# remote_control.net
KiCad netlist of a schematic drawn in EAGLE
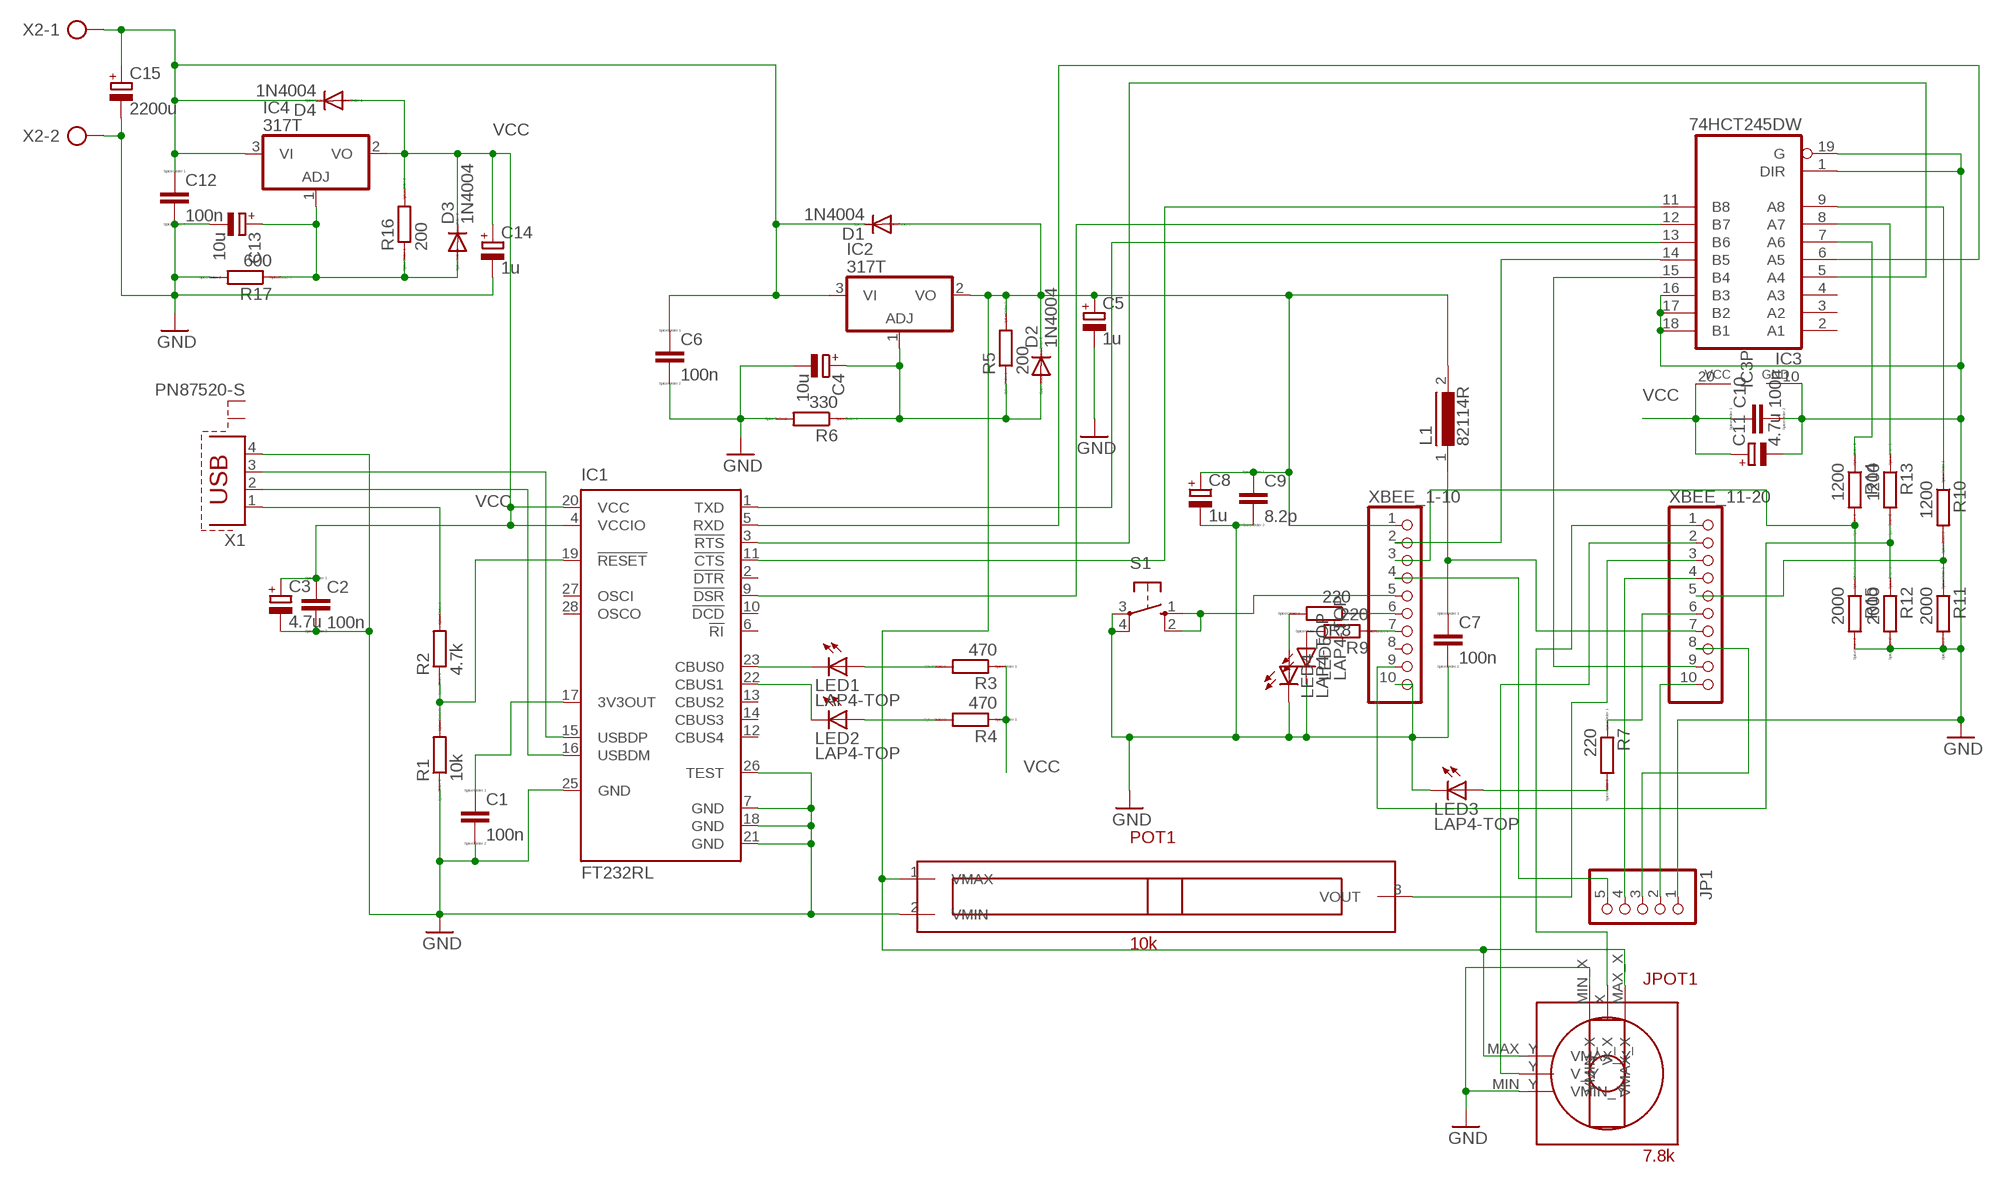
[diagram p0: schematic, sheet 1]

(export (version "E")
  (design (tool "Eeschema 10.0.6"))
  (components
    (comp (ref "C1")
      (value "100n")
      (footprint "eagle-import:C025-030X050")
      (libsource (lib "eagle-import") (part "C-EU025-030X050"))
    )
    (comp (ref "C2")
      (value "100n")
      (footprint "eagle-import:C0805K")
      (libsource (lib "eagle-import") (part "C-EUC0805K"))
    )
    (comp (ref "C3")
      (value "4.7u")
      (footprint "eagle-import:153CLV-0605")
      (libsource (lib "eagle-import") (part "CPOL-EU153CLV-0605"))
    )
    (comp (ref "C4")
      (value "10u")
      (footprint "eagle-import:E5-8,5")
      (libsource (lib "eagle-import") (part "CPOL-EUE5-8.5"))
    )
    (comp (ref "C5")
      (value "1u")
      (footprint "eagle-import:E5-8,5")
      (libsource (lib "eagle-import") (part "CPOL-EUE5-8.5"))
    )
    (comp (ref "C6")
      (value "100n")
      (footprint "eagle-import:C025-030X050")
      (libsource (lib "eagle-import") (part "C-EU025-030X050"))
    )
    (comp (ref "C7")
      (value "100n")
      (footprint "eagle-import:C025-030X050")
      (libsource (lib "eagle-import") (part "C-EU025-030X050"))
    )
    (comp (ref "C8")
      (value "1u")
      (footprint "eagle-import:E5-8,5")
      (libsource (lib "eagle-import") (part "CPOL-EUE5-8.5"))
    )
    (comp (ref "C9")
      (value "8.2p")
      (footprint "eagle-import:C025-030X050")
      (libsource (lib "eagle-import") (part "C-EU025-030X050"))
    )
    (comp (ref "C10")
      (value "100n")
      (footprint "eagle-import:C0805K")
      (libsource (lib "eagle-import") (part "C-EUC0805K"))
    )
    (comp (ref "C11")
      (value "4.7u")
      (footprint "eagle-import:153CLV-0605")
      (libsource (lib "eagle-import") (part "CPOL-EU153CLV-0605"))
    )
    (comp (ref "C12")
      (value "100n")
      (footprint "eagle-import:C025-030X050")
      (libsource (lib "eagle-import") (part "C-EU025-030X050"))
    )
    (comp (ref "C13")
      (value "10u")
      (footprint "eagle-import:E5-8,5")
      (libsource (lib "eagle-import") (part "CPOL-EUE5-8.5"))
    )
    (comp (ref "C14")
      (value "1u")
      (footprint "eagle-import:E5-8,5")
      (libsource (lib "eagle-import") (part "CPOL-EUE5-8.5"))
    )
    (comp (ref "C15")
      (value "2200u")
      (footprint "eagle-import:EB20D")
      (libsource (lib "eagle-import") (part "CPOL-EUE10-20"))
    )
    (comp (ref "D1")
      (value "1N4004")
      (footprint "eagle-import:DO41-10")
      (libsource (lib "eagle-import") (part "1N4004"))
    )
    (comp (ref "D2")
      (value "1N4004")
      (footprint "eagle-import:DO41-10")
      (libsource (lib "eagle-import") (part "1N4004"))
    )
    (comp (ref "D3")
      (value "1N4004")
      (footprint "eagle-import:DO41-10")
      (libsource (lib "eagle-import") (part "1N4004"))
    )
    (comp (ref "D4")
      (value "1N4004")
      (footprint "eagle-import:DO41-10")
      (libsource (lib "eagle-import") (part "1N4004"))
    )
    (comp (ref "IC1")
      (value "FT232RL")
      (footprint "eagle-import:SSOP28")
      (libsource (lib "eagle-import") (part "FT232RL"))
    )
    (comp (ref "IC2")
      (value "317T")
      (footprint "eagle-import:TO220H")
      (libsource (lib "eagle-import") (part "317T"))
    )
    (comp (ref "IC3")
      (value "74HCT245DW")
      (footprint "eagle-import:SO20W")
      (libsource (lib "eagle-import") (part "74245DWHCT"))
    )
    (comp (ref "IC4")
      (value "317T")
      (footprint "eagle-import:TO220H")
      (libsource (lib "eagle-import") (part "317T"))
    )
    (comp (ref "JP1")
      (value "PINHD-1X5")
      (footprint "eagle-import:1X05")
      (libsource (lib "eagle-import") (part "PINHD-1X5"))
    )
    (comp (ref "JPOT1")
      (value "7.8k")
      (footprint "eagle-import:DIL")
      (libsource (lib "eagle-import") (part "JOYSTICK_POTIP"))
    )
    (comp (ref "L1")
      (value "82114R")
      (footprint "eagle-import:82114R")
      (libsource (lib "eagle-import") (part "82114R"))
    )
    (comp (ref "LED1")
      (value "LAP4-TOP")
      (footprint "eagle-import:P47F-TOP")
      (libsource (lib "eagle-import") (part "P4-TOPLA"))
    )
    (comp (ref "LED2")
      (value "LAP4-TOP")
      (footprint "eagle-import:P47F-TOP")
      (libsource (lib "eagle-import") (part "P4-TOPLA"))
    )
    (comp (ref "LED3")
      (value "LAP4-TOP")
      (footprint "eagle-import:P47F-TOP")
      (libsource (lib "eagle-import") (part "P4-TOPLA"))
    )
    (comp (ref "LED4")
      (value "LAP4-TOP")
      (footprint "eagle-import:P47F-TOP")
      (libsource (lib "eagle-import") (part "P4-TOPLA"))
    )
    (comp (ref "LED5")
      (value "LAP4-TOP")
      (footprint "eagle-import:P47F-TOP")
      (libsource (lib "eagle-import") (part "P4-TOPLA"))
    )
    (comp (ref "POT1")
      (value "10k")
      (footprint "eagle-import:DIL")
      (libsource (lib "eagle-import") (part "SCHIEBEPOTENTIOMETER"))
    )
    (comp (ref "R1")
      (value "10k")
      (footprint "eagle-import:0207_10")
      (libsource (lib "eagle-import") (part "R-EU_0207_10"))
    )
    (comp (ref "R2")
      (value "4.7k")
      (footprint "eagle-import:0207_10")
      (libsource (lib "eagle-import") (part "R-EU_0207_10"))
    )
    (comp (ref "R3")
      (value "470")
      (footprint "eagle-import:0207_10")
      (libsource (lib "eagle-import") (part "R-EU_0207_10"))
    )
    (comp (ref "R4")
      (value "470")
      (footprint "eagle-import:0207_10")
      (libsource (lib "eagle-import") (part "R-EU_0207_10"))
    )
    (comp (ref "R5")
      (value "200")
      (footprint "eagle-import:0411_15")
      (libsource (lib "eagle-import") (part "R-EU_0411_15"))
    )
    (comp (ref "R6")
      (value "330")
      (footprint "eagle-import:0411_15")
      (libsource (lib "eagle-import") (part "R-EU_0411_15"))
    )
    (comp (ref "R7")
      (value "220")
      (footprint "eagle-import:0207_10")
      (libsource (lib "eagle-import") (part "R-EU_0207_10"))
    )
    (comp (ref "R8")
      (value "220")
      (footprint "eagle-import:0207_10")
      (libsource (lib "eagle-import") (part "R-EU_0207_10"))
    )
    (comp (ref "R9")
      (value "220")
      (footprint "eagle-import:0207_10")
      (libsource (lib "eagle-import") (part "R-EU_0207_10"))
    )
    (comp (ref "R10")
      (value "1200")
      (footprint "eagle-import:0207_10")
      (libsource (lib "eagle-import") (part "R-EU_0207_10"))
    )
    (comp (ref "R11")
      (value "2000")
      (footprint "eagle-import:0207_10")
      (libsource (lib "eagle-import") (part "R-EU_0207_10"))
    )
    (comp (ref "R12")
      (value "2000")
      (footprint "eagle-import:0207_10")
      (libsource (lib "eagle-import") (part "R-EU_0207_10"))
    )
    (comp (ref "R13")
      (value "1200")
      (footprint "eagle-import:0207_10")
      (libsource (lib "eagle-import") (part "R-EU_0207_10"))
    )
    (comp (ref "R14")
      (value "1200")
      (footprint "eagle-import:0207_10")
      (libsource (lib "eagle-import") (part "R-EU_0207_10"))
    )
    (comp (ref "R15")
      (value "2000")
      (footprint "eagle-import:0207_10")
      (libsource (lib "eagle-import") (part "R-EU_0207_10"))
    )
    (comp (ref "R16")
      (value "200")
      (footprint "eagle-import:0411_15")
      (libsource (lib "eagle-import") (part "R-EU_0411_15"))
    )
    (comp (ref "R17")
      (value "600")
      (footprint "eagle-import:0411_15")
      (libsource (lib "eagle-import") (part "R-EU_0411_15"))
    )
    (comp (ref "S1")
      (value "40-XX")
      (footprint "eagle-import:B3F-40XX")
      (fields (field (name "MF") "OMRON COMPONENTS USA") (field (name "MPN") "B3F-4000"))
      (libsource (lib "eagle-import") (part "40-XX"))
    )
    (comp (ref "X1")
      (value "PN87520-S")
      (footprint "eagle-import:PN87520-S")
      (libsource (lib "eagle-import") (part "PN87520-S"))
    )
    (comp (ref "X2")
      (value "AK300/2")
      (footprint "eagle-import:AK300_2")
      (libsource (lib "eagle-import") (part "AK300/2"))
    )
    (comp (ref "XBEE_1-10")
      (value "PINHD-1X10M")
      (footprint "eagle-import:1X10M")
      (libsource (lib "eagle-import") (part "PINHD-1X10M"))
    )
    (comp (ref "XBEE_11-20")
      (value "PINHD-1X10M")
      (footprint "eagle-import:1X10M")
      (libsource (lib "eagle-import") (part "PINHD-1X10M"))
    )
  )
  (nets
    (net (code "1") (name "/VCC") (class "Default")
      (node (ref "C10") (pin "1") (pinfunction "1_1") (pintype "passive"))
      (node (ref "C11") (pin "+") (pinfunction "+_+") (pintype "passive"))
      (node (ref "C14") (pin "+") (pinfunction "+_+") (pintype "passive"))
      (node (ref "C2") (pin "1") (pinfunction "1_1") (pintype "passive"))
      (node (ref "C3") (pin "+") (pinfunction "+_+") (pintype "passive"))
      (node (ref "D3") (pin "C") (pinfunction "C_C") (pintype "passive"))
      (node (ref "D4") (pin "A") (pinfunction "A_A") (pintype "passive"))
      (node (ref "IC1") (pin "20") (pinfunction "VCC_20") (pintype "power_in"))
      (node (ref "IC1") (pin "4") (pinfunction "VCCIO_4") (pintype "power_in"))
      (node (ref "IC3") (pin "20") (pinfunction "VCC_20") (pintype "power_in"))
      (node (ref "IC4") (pin "2") (pinfunction "VO_2") (pintype "passive"))
      (node (ref "R16") (pin "2") (pinfunction "2_2") (pintype "passive"))
      (node (ref "R3") (pin "1") (pinfunction "1_1") (pintype "passive"))
      (node (ref "R4") (pin "1") (pinfunction "1_1") (pintype "passive"))
    )
    (net (code "2") (name "GND") (class "Default")
      (node (ref "C1") (pin "2") (pinfunction "2_2") (pintype "passive"))
      (node (ref "C10") (pin "2") (pinfunction "2_2") (pintype "passive"))
      (node (ref "C11") (pin "-") (pinfunction "-_-") (pintype "passive"))
      (node (ref "C12") (pin "2") (pinfunction "2_2") (pintype "passive"))
      (node (ref "C13") (pin "-") (pinfunction "-_-") (pintype "passive"))
      (node (ref "C14") (pin "-") (pinfunction "-_-") (pintype "passive"))
      (node (ref "C15") (pin "-") (pinfunction "-_-") (pintype "passive"))
      (node (ref "C2") (pin "2") (pinfunction "2_2") (pintype "passive"))
      (node (ref "C3") (pin "-") (pinfunction "-_-") (pintype "passive"))
      (node (ref "C4") (pin "-") (pinfunction "-_-") (pintype "passive"))
      (node (ref "C5") (pin "-") (pinfunction "-_-") (pintype "passive"))
      (node (ref "C6") (pin "2") (pinfunction "2_2") (pintype "passive"))
      (node (ref "C7") (pin "2") (pinfunction "2_2") (pintype "passive"))
      (node (ref "C8") (pin "-") (pinfunction "-_-") (pintype "passive"))
      (node (ref "C9") (pin "2") (pinfunction "2_2") (pintype "passive"))
      (node (ref "IC1") (pin "18") (pinfunction "GND_18") (pintype "power_in"))
      (node (ref "IC1") (pin "21") (pinfunction "GND_21") (pintype "power_in"))
      (node (ref "IC1") (pin "25") (pinfunction "GND_25") (pintype "power_in"))
      (node (ref "IC1") (pin "26") (pinfunction "TEST_26") (pintype "input"))
      (node (ref "IC1") (pin "7") (pinfunction "GND_7") (pintype "power_in"))
      (node (ref "IC3") (pin "1") (pinfunction "DIR_1") (pintype "input"))
      (node (ref "IC3") (pin "10") (pinfunction "GND_10") (pintype "power_in"))
      (node (ref "IC3") (pin "16") (pinfunction "B3_16") (pintype "bidirectional"))
      (node (ref "IC3") (pin "17") (pinfunction "B2_17") (pintype "bidirectional"))
      (node (ref "IC3") (pin "18") (pinfunction "B1_18") (pintype "bidirectional"))
      (node (ref "IC3") (pin "19") (pinfunction "G_19") (pintype "input"))
      (node (ref "JP1") (pin "1") (pinfunction "1_1") (pintype "passive"))
      (node (ref "JPOT1") (pin "MIN_X") (pinfunction "VMIN_X_MIN_X") (pintype "bidirectional"))
      (node (ref "JPOT1") (pin "MIN_Y") (pinfunction "VMIN_Y_MIN_Y") (pintype "bidirectional"))
      (node (ref "LED3") (pin "C") (pinfunction "C_C") (pintype "passive"))
      (node (ref "LED4") (pin "C") (pinfunction "C_C") (pintype "passive"))
      (node (ref "LED5") (pin "C") (pinfunction "C_C") (pintype "passive"))
      (node (ref "POT1") (pin "2") (pinfunction "VMIN_2") (pintype "input"))
      (node (ref "R1") (pin "1") (pinfunction "1_1") (pintype "passive"))
      (node (ref "R11") (pin "2") (pinfunction "2_2") (pintype "passive"))
      (node (ref "R12") (pin "2") (pinfunction "2_2") (pintype "passive"))
      (node (ref "R15") (pin "2") (pinfunction "2_2") (pintype "passive"))
      (node (ref "R17") (pin "2") (pinfunction "2_2") (pintype "passive"))
      (node (ref "R6") (pin "2") (pinfunction "2_2") (pintype "passive"))
      (node (ref "S1") (pin "3") (pinfunction "P_3") (pintype "passive"))
      (node (ref "S1") (pin "4") (pinfunction "P1_4") (pintype "passive"))
      (node (ref "X1") (pin "4") (pinfunction "4_4") (pintype "passive"))
      (node (ref "X2") (pin "2") (pinfunction "KL_2") (pintype "passive"))
      (node (ref "XBEE_1-10") (pin "10") (pinfunction "10_10") (pintype "passive"))
    )
    (net (code "3") (name "Net-(C7-Pad1)") (class "Default")
      (node (ref "C7") (pin "1") (pinfunction "1_1") (pintype "passive"))
      (node (ref "L1") (pin "1") (pinfunction "1_1") (pintype "passive"))
      (node (ref "XBEE_11-20") (pin "7") (pinfunction "7_7") (pintype "passive"))
    )
    (net (code "4") (name "Net-(IC1-3V3OUT)") (class "Default")
      (node (ref "C1") (pin "1") (pinfunction "1_1") (pintype "passive"))
      (node (ref "IC1") (pin "17") (pinfunction "3V3OUT_17") (pintype "output"))
    )
    (net (code "5") (name "Net-(IC1-CBUS0)") (class "Default")
      (node (ref "IC1") (pin "23") (pinfunction "CBUS0_23") (pintype "bidirectional"))
      (node (ref "LED1") (pin "C") (pinfunction "C_C") (pintype "passive"))
    )
    (net (code "6") (name "Net-(IC1-CBUS1)") (class "Default")
      (node (ref "IC1") (pin "22") (pinfunction "CBUS1_22") (pintype "bidirectional"))
      (node (ref "LED2") (pin "C") (pinfunction "C_C") (pintype "passive"))
    )
    (net (code "7") (name "Net-(IC1-RXD)") (class "Default")
      (node (ref "IC1") (pin "5") (pinfunction "RXD_5") (pintype "input"))
      (node (ref "IC3") (pin "6") (pinfunction "A5_6") (pintype "bidirectional"))
    )
    (net (code "8") (name "Net-(IC1-TXD)") (class "Default")
      (node (ref "IC1") (pin "1") (pinfunction "TXD_1") (pintype "output"))
      (node (ref "IC3") (pin "13") (pinfunction "B6_13") (pintype "bidirectional"))
    )
    (net (code "9") (name "Net-(IC1-USBDM)") (class "Default")
      (node (ref "IC1") (pin "16") (pinfunction "USBDM_16") (pintype "bidirectional"))
      (node (ref "X1") (pin "2") (pinfunction "2_2") (pintype "passive"))
    )
    (net (code "10") (name "Net-(IC1-USBDP)") (class "Default")
      (node (ref "IC1") (pin "15") (pinfunction "USBDP_15") (pintype "bidirectional"))
      (node (ref "X1") (pin "3") (pinfunction "3_3") (pintype "passive"))
    )
    (net (code "11") (name "Net-(IC1-~{CTS})") (class "Default")
      (node (ref "IC1") (pin "11") (pinfunction "~{CTS}_11") (pintype "input"))
      (node (ref "IC3") (pin "11") (pinfunction "B8_11") (pintype "bidirectional"))
    )
    (net (code "12") (name "Net-(IC1-~{DSR})") (class "Default")
      (node (ref "IC1") (pin "9") (pinfunction "~{DSR}_9") (pintype "input"))
      (node (ref "IC3") (pin "12") (pinfunction "B7_12") (pintype "bidirectional"))
    )
    (net (code "13") (name "Net-(IC1-~{RESET})") (class "Default")
      (node (ref "IC1") (pin "19") (pinfunction "~{RESET}_19") (pintype "input"))
      (node (ref "R1") (pin "2") (pinfunction "2_2") (pintype "passive"))
      (node (ref "R2") (pin "1") (pinfunction "1_1") (pintype "passive"))
    )
    (net (code "14") (name "Net-(IC1-~{RTS})") (class "Default")
      (node (ref "IC1") (pin "3") (pinfunction "~{RTS}_3") (pintype "output"))
      (node (ref "IC3") (pin "5") (pinfunction "A4_5") (pintype "bidirectional"))
    )
    (net (code "15") (name "Net-(IC2-ADJ)") (class "Default")
      (node (ref "C4") (pin "+") (pinfunction "+_+") (pintype "passive"))
      (node (ref "D2") (pin "A") (pinfunction "A_A") (pintype "passive"))
      (node (ref "IC2") (pin "1") (pinfunction "ADJ_1") (pintype "input"))
      (node (ref "R5") (pin "1") (pinfunction "1_1") (pintype "passive"))
      (node (ref "R6") (pin "1") (pinfunction "1_1") (pintype "passive"))
    )
    (net (code "16") (name "Net-(IC2-VI)") (class "Default")
      (node (ref "C12") (pin "1") (pinfunction "1_1") (pintype "passive"))
      (node (ref "C15") (pin "+") (pinfunction "+_+") (pintype "passive"))
      (node (ref "C6") (pin "1") (pinfunction "1_1") (pintype "passive"))
      (node (ref "D1") (pin "C") (pinfunction "C_C") (pintype "passive"))
      (node (ref "D4") (pin "C") (pinfunction "C_C") (pintype "passive"))
      (node (ref "IC2") (pin "3") (pinfunction "VI_3") (pintype "input"))
      (node (ref "IC4") (pin "3") (pinfunction "VI_3") (pintype "input"))
      (node (ref "X2") (pin "1") (pinfunction "KL_1") (pintype "passive"))
    )
    (net (code "17") (name "Net-(IC2-VO)") (class "Default")
      (node (ref "C5") (pin "+") (pinfunction "+_+") (pintype "passive"))
      (node (ref "C8") (pin "+") (pinfunction "+_+") (pintype "passive"))
      (node (ref "C9") (pin "1") (pinfunction "1_1") (pintype "passive"))
      (node (ref "D1") (pin "A") (pinfunction "A_A") (pintype "passive"))
      (node (ref "D2") (pin "C") (pinfunction "C_C") (pintype "passive"))
      (node (ref "IC2") (pin "2") (pinfunction "VO_2") (pintype "passive"))
      (node (ref "JPOT1") (pin "MAX_X") (pinfunction "VMAX_X_MAX_X") (pintype "bidirectional"))
      (node (ref "JPOT1") (pin "MAX_Y") (pinfunction "VMAX_Y_MAX_Y") (pintype "bidirectional"))
      (node (ref "L1") (pin "2") (pinfunction "2_2") (pintype "passive"))
      (node (ref "POT1") (pin "1") (pinfunction "VMAX_1") (pintype "input"))
      (node (ref "R5") (pin "2") (pinfunction "2_2") (pintype "passive"))
      (node (ref "XBEE_1-10") (pin "1") (pinfunction "1_1") (pintype "passive"))
    )
    (net (code "18") (name "Net-(IC3A-A6)") (class "Default")
      (node (ref "IC3") (pin "7") (pinfunction "A6_7") (pintype "bidirectional"))
      (node (ref "R14") (pin "1") (pinfunction "1_1") (pintype "passive"))
    )
    (net (code "19") (name "Net-(IC3A-A7)") (class "Default")
      (node (ref "IC3") (pin "8") (pinfunction "A7_8") (pintype "bidirectional"))
      (node (ref "R13") (pin "1") (pinfunction "1_1") (pintype "passive"))
    )
    (net (code "20") (name "Net-(IC3A-A8)") (class "Default")
      (node (ref "IC3") (pin "9") (pinfunction "A8_9") (pintype "bidirectional"))
      (node (ref "R10") (pin "1") (pinfunction "1_1") (pintype "passive"))
    )
    (net (code "21") (name "Net-(IC3A-B4)") (class "Default")
      (node (ref "IC3") (pin "15") (pinfunction "B4_15") (pintype "bidirectional"))
      (node (ref "XBEE_11-20") (pin "9") (pinfunction "9_9") (pintype "passive"))
    )
    (net (code "22") (name "Net-(IC3A-B5)") (class "Default")
      (node (ref "IC3") (pin "14") (pinfunction "B5_14") (pintype "bidirectional"))
      (node (ref "XBEE_1-10") (pin "2") (pinfunction "2_2") (pintype "passive"))
    )
    (net (code "23") (name "Net-(IC4-ADJ)") (class "Default")
      (node (ref "C13") (pin "+") (pinfunction "+_+") (pintype "passive"))
      (node (ref "D3") (pin "A") (pinfunction "A_A") (pintype "passive"))
      (node (ref "IC4") (pin "1") (pinfunction "ADJ_1") (pintype "input"))
      (node (ref "R16") (pin "1") (pinfunction "1_1") (pintype "passive"))
      (node (ref "R17") (pin "1") (pinfunction "1_1") (pintype "passive"))
    )
    (net (code "24") (name "Net-(JP1-Pad2)") (class "Default")
      (node (ref "JP1") (pin "2") (pinfunction "2_2") (pintype "passive"))
      (node (ref "XBEE_11-20") (pin "10") (pinfunction "10_10") (pintype "passive"))
    )
    (net (code "25") (name "Net-(JP1-Pad3)") (class "Default")
      (node (ref "JP1") (pin "3") (pinfunction "3_3") (pintype "passive"))
      (node (ref "XBEE_11-20") (pin "8") (pinfunction "8_8") (pintype "passive"))
    )
    (net (code "26") (name "Net-(JP1-Pad4)") (class "Default")
      (node (ref "JP1") (pin "4") (pinfunction "4_4") (pintype "passive"))
      (node (ref "XBEE_11-20") (pin "4") (pinfunction "4_4") (pintype "passive"))
    )
    (net (code "27") (name "Net-(JP1-Pad5)") (class "Default")
      (node (ref "JP1") (pin "5") (pinfunction "5_5") (pintype "passive"))
      (node (ref "XBEE_1-10") (pin "4") (pinfunction "4_4") (pintype "passive"))
    )
    (net (code "28") (name "Net-(JPOT1-V_X)") (class "Default")
      (node (ref "JPOT1") (pin "X") (pinfunction "V_X_X") (pintype "bidirectional"))
      (node (ref "XBEE_11-20") (pin "1") (pinfunction "1_1") (pintype "passive"))
    )
    (net (code "29") (name "Net-(JPOT1-V_Y)") (class "Default")
      (node (ref "JPOT1") (pin "Y") (pinfunction "V_Y_Y") (pintype "bidirectional"))
      (node (ref "XBEE_11-20") (pin "2") (pinfunction "2_2") (pintype "passive"))
    )
    (net (code "30") (name "Net-(LED1-PadA)") (class "Default")
      (node (ref "LED1") (pin "A") (pinfunction "A_A") (pintype "passive"))
      (node (ref "R3") (pin "2") (pinfunction "2_2") (pintype "passive"))
    )
    (net (code "31") (name "Net-(LED2-PadA)") (class "Default")
      (node (ref "LED2") (pin "A") (pinfunction "A_A") (pintype "passive"))
      (node (ref "R4") (pin "2") (pinfunction "2_2") (pintype "passive"))
    )
    (net (code "32") (name "Net-(LED3-PadA)") (class "Default")
      (node (ref "LED3") (pin "A") (pinfunction "A_A") (pintype "passive"))
      (node (ref "R7") (pin "2") (pinfunction "2_2") (pintype "passive"))
    )
    (net (code "33") (name "Net-(LED4-PadA)") (class "Default")
      (node (ref "LED4") (pin "A") (pinfunction "A_A") (pintype "passive"))
      (node (ref "R8") (pin "2") (pinfunction "2_2") (pintype "passive"))
    )
    (net (code "34") (name "Net-(LED5-PadA)") (class "Default")
      (node (ref "LED5") (pin "A") (pinfunction "A_A") (pintype "passive"))
      (node (ref "R9") (pin "2") (pinfunction "2_2") (pintype "passive"))
    )
    (net (code "35") (name "Net-(POT1-VOUT)") (class "Default")
      (node (ref "POT1") (pin "3") (pinfunction "VOUT_3") (pintype "output"))
      (node (ref "XBEE_11-20") (pin "3") (pinfunction "3_3") (pintype "passive"))
    )
    (net (code "36") (name "Net-(R2-Pad2)") (class "Default")
      (node (ref "R2") (pin "2") (pinfunction "2_2") (pintype "passive"))
      (node (ref "X1") (pin "1") (pinfunction "1_1") (pintype "passive"))
    )
    (net (code "37") (name "Net-(R7-Pad1)") (class "Default")
      (node (ref "R7") (pin "1") (pinfunction "1_1") (pintype "passive"))
      (node (ref "XBEE_11-20") (pin "6") (pinfunction "6_6") (pintype "passive"))
    )
    (net (code "38") (name "Net-(R8-Pad1)") (class "Default")
      (node (ref "R8") (pin "1") (pinfunction "1_1") (pintype "passive"))
      (node (ref "XBEE_1-10") (pin "6") (pinfunction "6_6") (pintype "passive"))
    )
    (net (code "39") (name "Net-(R9-Pad1)") (class "Default")
      (node (ref "R9") (pin "1") (pinfunction "1_1") (pintype "passive"))
      (node (ref "XBEE_1-10") (pin "7") (pinfunction "7_7") (pintype "passive"))
    )
    (net (code "40") (name "Net-(R10-Pad2)") (class "Default")
      (node (ref "R10") (pin "2") (pinfunction "2_2") (pintype "passive"))
      (node (ref "R11") (pin "1") (pinfunction "1_1") (pintype "passive"))
      (node (ref "XBEE_11-20") (pin "5") (pinfunction "5_5") (pintype "passive"))
    )
    (net (code "41") (name "Net-(R12-Pad1)") (class "Default")
      (node (ref "R12") (pin "1") (pinfunction "1_1") (pintype "passive"))
      (node (ref "R13") (pin "2") (pinfunction "2_2") (pintype "passive"))
      (node (ref "XBEE_1-10") (pin "9") (pinfunction "9_9") (pintype "passive"))
    )
    (net (code "42") (name "Net-(R14-Pad2)") (class "Default")
      (node (ref "R14") (pin "2") (pinfunction "2_2") (pintype "passive"))
      (node (ref "R15") (pin "1") (pinfunction "1_1") (pintype "passive"))
      (node (ref "XBEE_1-10") (pin "3") (pinfunction "3_3") (pintype "passive"))
    )
    (net (code "43") (name "Net-(S1-S)") (class "Default")
      (node (ref "S1") (pin "1") (pinfunction "S_1") (pintype "passive"))
      (node (ref "S1") (pin "2") (pinfunction "S1_2") (pintype "passive"))
      (node (ref "XBEE_1-10") (pin "5") (pinfunction "5_5") (pintype "passive"))
    )
    (net (code "44") (name "unconnected-(IC1-CBUS2-Pad13)") (class "Default")
      (node (ref "IC1") (pin "13") (pinfunction "CBUS2_13") (pintype "bidirectional"))
    )
    (net (code "45") (name "unconnected-(IC1-CBUS3-Pad14)") (class "Default")
      (node (ref "IC1") (pin "14") (pinfunction "CBUS3_14") (pintype "bidirectional"))
    )
    (net (code "46") (name "unconnected-(IC1-CBUS4-Pad12)") (class "Default")
      (node (ref "IC1") (pin "12") (pinfunction "CBUS4_12") (pintype "bidirectional"))
    )
    (net (code "47") (name "unconnected-(IC1-OSCI-Pad27)") (class "Default")
      (node (ref "IC1") (pin "27") (pinfunction "OSCI_27") (pintype "input"))
    )
    (net (code "48") (name "unconnected-(IC1-OSCO-Pad28)") (class "Default")
      (node (ref "IC1") (pin "28") (pinfunction "OSCO_28") (pintype "output"))
    )
    (net (code "49") (name "unconnected-(IC1-~{DCD}-Pad10)") (class "Default")
      (node (ref "IC1") (pin "10") (pinfunction "~{DCD}_10") (pintype "input"))
    )
    (net (code "50") (name "unconnected-(IC1-~{DTR}-Pad2)") (class "Default")
      (node (ref "IC1") (pin "2") (pinfunction "~{DTR}_2") (pintype "output"))
    )
    (net (code "51") (name "unconnected-(IC1-~{RI}-Pad6)") (class "Default")
      (node (ref "IC1") (pin "6") (pinfunction "~{RI}_6") (pintype "input"))
    )
    (net (code "52") (name "unconnected-(IC3A-A1-Pad2)") (class "Default")
      (node (ref "IC3") (pin "2") (pinfunction "A1_2") (pintype "bidirectional"))
    )
    (net (code "53") (name "unconnected-(IC3A-A2-Pad3)") (class "Default")
      (node (ref "IC3") (pin "3") (pinfunction "A2_3") (pintype "bidirectional"))
    )
    (net (code "54") (name "unconnected-(IC3A-A3-Pad4)") (class "Default")
      (node (ref "IC3") (pin "4") (pinfunction "A3_4") (pintype "bidirectional"))
    )
    (net (code "55") (name "unconnected-(X1-PadS1)") (class "Default")
      (node (ref "X1") (pin "S1") (pinfunction "S1_S1") (pintype "passive"))
    )
    (net (code "56") (name "unconnected-(X1-PadS2)") (class "Default")
      (node (ref "X1") (pin "S2") (pinfunction "S2_S2") (pintype "passive"))
    )
    (net (code "57") (name "unconnected-(XBEE_1-10-Pad8)") (class "Default")
      (node (ref "XBEE_1-10") (pin "8") (pinfunction "8_8") (pintype "passive"))
    )
  )
)
